# Lemming_v3.net
KiCad netlist of a schematic drawn in EAGLE
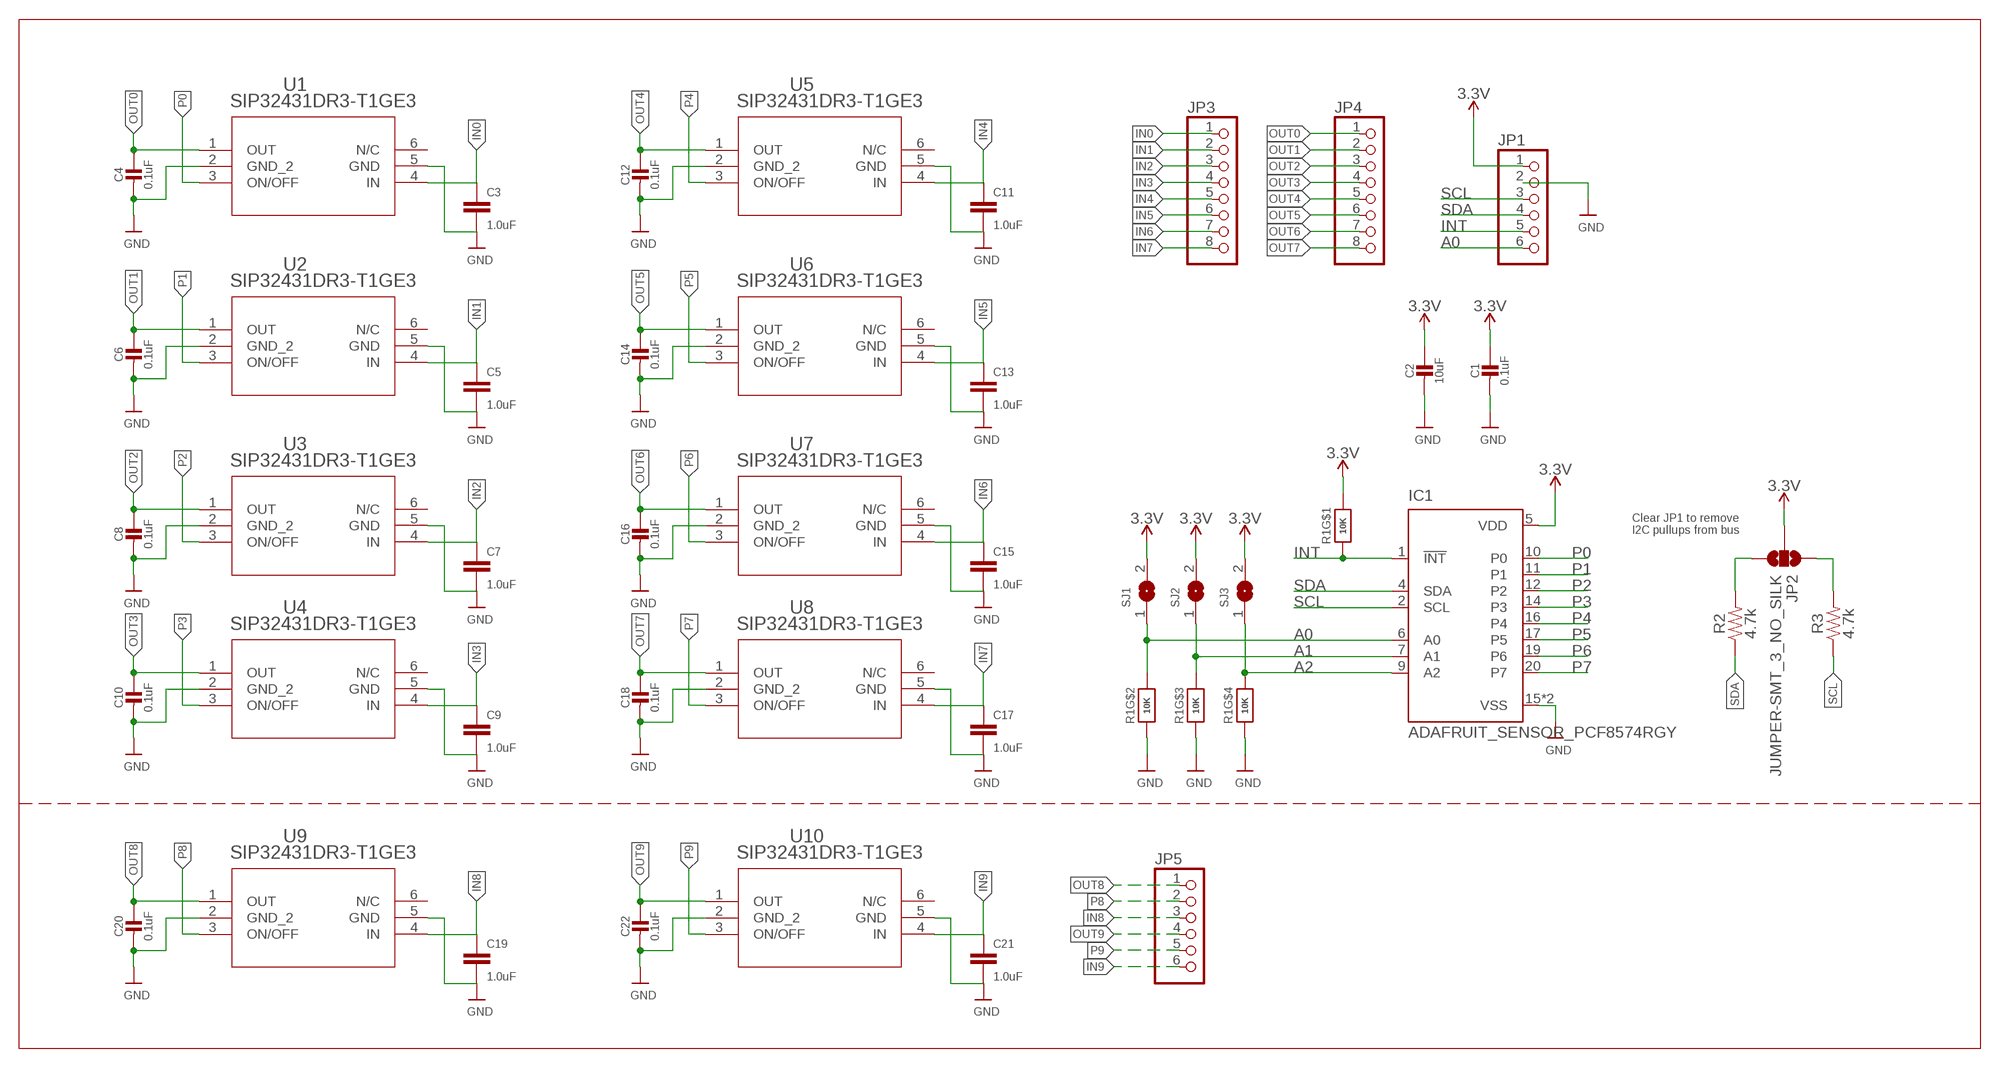
[diagram p0: schematic, sheet 1]

(export (version "E")
  (design (tool "Eeschema 10.0.6"))
  (components
    (comp (ref "C1")
      (value "0.1uF")
      (footprint "eagle-import:0603-NO")
      (libsource (lib "eagle-import") (part "CAP_CERAMIC0603_NO"))
    )
    (comp (ref "C2")
      (value "10uF")
      (footprint "eagle-import:0805-NO")
      (libsource (lib "eagle-import") (part "CAP_CERAMIC0805-NOOUTLINE"))
    )
    (comp (ref "C3")
      (value "1.0uF")
      (footprint "eagle-import:0603")
      (libsource (lib "eagle-import") (part "1.0UF-0603-16V-10%"))
    )
    (comp (ref "C4")
      (value "0.1uF")
      (footprint "eagle-import:0603-NO")
      (libsource (lib "eagle-import") (part "CAP_CERAMIC0603_NO"))
    )
    (comp (ref "C5")
      (value "1.0uF")
      (footprint "eagle-import:0603")
      (libsource (lib "eagle-import") (part "1.0UF-0603-16V-10%"))
    )
    (comp (ref "C6")
      (value "0.1uF")
      (footprint "eagle-import:0603-NO")
      (libsource (lib "eagle-import") (part "CAP_CERAMIC0603_NO"))
    )
    (comp (ref "C7")
      (value "1.0uF")
      (footprint "eagle-import:0603")
      (libsource (lib "eagle-import") (part "1.0UF-0603-16V-10%"))
    )
    (comp (ref "C8")
      (value "0.1uF")
      (footprint "eagle-import:0603-NO")
      (libsource (lib "eagle-import") (part "CAP_CERAMIC0603_NO"))
    )
    (comp (ref "C9")
      (value "1.0uF")
      (footprint "eagle-import:0603")
      (libsource (lib "eagle-import") (part "1.0UF-0603-16V-10%"))
    )
    (comp (ref "C10")
      (value "0.1uF")
      (footprint "eagle-import:0603-NO")
      (libsource (lib "eagle-import") (part "CAP_CERAMIC0603_NO"))
    )
    (comp (ref "C11")
      (value "1.0uF")
      (footprint "eagle-import:0603")
      (libsource (lib "eagle-import") (part "1.0UF-0603-16V-10%"))
    )
    (comp (ref "C12")
      (value "0.1uF")
      (footprint "eagle-import:0603-NO")
      (libsource (lib "eagle-import") (part "CAP_CERAMIC0603_NO"))
    )
    (comp (ref "C13")
      (value "1.0uF")
      (footprint "eagle-import:0603")
      (libsource (lib "eagle-import") (part "1.0UF-0603-16V-10%"))
    )
    (comp (ref "C14")
      (value "0.1uF")
      (footprint "eagle-import:0603-NO")
      (libsource (lib "eagle-import") (part "CAP_CERAMIC0603_NO"))
    )
    (comp (ref "C15")
      (value "1.0uF")
      (footprint "eagle-import:0603")
      (libsource (lib "eagle-import") (part "1.0UF-0603-16V-10%"))
    )
    (comp (ref "C16")
      (value "0.1uF")
      (footprint "eagle-import:0603-NO")
      (libsource (lib "eagle-import") (part "CAP_CERAMIC0603_NO"))
    )
    (comp (ref "C17")
      (value "1.0uF")
      (footprint "eagle-import:0603")
      (libsource (lib "eagle-import") (part "1.0UF-0603-16V-10%"))
    )
    (comp (ref "C18")
      (value "0.1uF")
      (footprint "eagle-import:0603-NO")
      (libsource (lib "eagle-import") (part "CAP_CERAMIC0603_NO"))
    )
    (comp (ref "C19")
      (value "1.0uF")
      (footprint "eagle-import:0603")
      (libsource (lib "eagle-import") (part "1.0UF-0603-16V-10%"))
    )
    (comp (ref "C20")
      (value "0.1uF")
      (footprint "eagle-import:0603-NO")
      (libsource (lib "eagle-import") (part "CAP_CERAMIC0603_NO"))
    )
    (comp (ref "C21")
      (value "1.0uF")
      (footprint "eagle-import:0603")
      (libsource (lib "eagle-import") (part "1.0UF-0603-16V-10%"))
    )
    (comp (ref "C22")
      (value "0.1uF")
      (footprint "eagle-import:0603-NO")
      (libsource (lib "eagle-import") (part "CAP_CERAMIC0603_NO"))
    )
    (comp (ref "IC1")
      (value "ADAFRUIT_SENSOR_PCF8574RGY")
      (footprint "eagle-import:ADAFRUIT_SENSOR_VQFN20_3.5X4.5")
      (libsource (lib "eagle-import") (part "ADAFRUIT_SENSOR_PCF8574RGY"))
    )
    (comp (ref "JP1")
      (value "HEADER-1X670MIL")
      (footprint "eagle-import:1X06_ROUND_70")
      (libsource (lib "eagle-import") (part "HEADER-1X670MIL"))
    )
    (comp (ref "JP2")
      (value "JUMPER-SMT_3_NO_SILK")
      (footprint "eagle-import:SMT-JUMPER_3_NO_SILK")
      (libsource (lib "eagle-import") (part "JUMPER-SMT_3_NO_SILK"))
    )
    (comp (ref "JP3")
      (value "PINHD-1X8BIG")
      (footprint "eagle-import:1X08-BIG")
      (libsource (lib "eagle-import") (part "PINHD-1X8BIG"))
    )
    (comp (ref "JP4")
      (value "PINHD-1X8BIG")
      (footprint "eagle-import:1X08-BIG")
      (libsource (lib "eagle-import") (part "PINHD-1X8BIG"))
    )
    (comp (ref "JP5")
      (value "HEADER-1X670MIL")
      (footprint "eagle-import:1X06_ROUND_70")
      (libsource (lib "eagle-import") (part "HEADER-1X670MIL"))
    )
    (comp (ref "R1")
      (value "10K")
      (footprint "eagle-import:MICROBUILDER_RESPACK_4X0603")
      (libsource (lib "eagle-import") (part "MICROBUILDER_RESISTOR_4PACK"))
    )
    (comp (ref "R2")
      (value "4.7k")
      (footprint "eagle-import:0603")
      (libsource (lib "eagle-import") (part "4.7KOHM-0603-1/10W-1%"))
    )
    (comp (ref "R3")
      (value "4.7k")
      (footprint "eagle-import:0603")
      (libsource (lib "eagle-import") (part "4.7KOHM-0603-1/10W-1%"))
    )
    (comp (ref "SJ1")
      (value "SOLDERJUMPER")
      (footprint "eagle-import:SOLDERJUMPER_ARROW_NOPASTE")
      (libsource (lib "eagle-import") (part "SOLDERJUMPER"))
    )
    (comp (ref "SJ2")
      (value "SOLDERJUMPER")
      (footprint "eagle-import:SOLDERJUMPER_ARROW_NOPASTE")
      (libsource (lib "eagle-import") (part "SOLDERJUMPER"))
    )
    (comp (ref "SJ3")
      (value "SOLDERJUMPER")
      (footprint "eagle-import:SOLDERJUMPER_ARROW_NOPASTE")
      (libsource (lib "eagle-import") (part "SOLDERJUMPER"))
    )
    (comp (ref "U1")
      (value "SIP32431DR3-T1GE3")
      (footprint "eagle-import:SC-70-6_VIS")
      (fields (field (name "COPYRIGHT") "Copyright (C) 2022 Ultra Librarian. All rights reserved."))
      (libsource (lib "eagle-import") (part "SIP32431DR3-T1GE3"))
    )
    (comp (ref "U2")
      (value "SIP32431DR3-T1GE3")
      (footprint "eagle-import:SC-70-6_VIS")
      (fields (field (name "COPYRIGHT") "Copyright (C) 2022 Ultra Librarian. All rights reserved."))
      (libsource (lib "eagle-import") (part "SIP32431DR3-T1GE3"))
    )
    (comp (ref "U3")
      (value "SIP32431DR3-T1GE3")
      (footprint "eagle-import:SC-70-6_VIS")
      (fields (field (name "COPYRIGHT") "Copyright (C) 2022 Ultra Librarian. All rights reserved."))
      (libsource (lib "eagle-import") (part "SIP32431DR3-T1GE3"))
    )
    (comp (ref "U4")
      (value "SIP32431DR3-T1GE3")
      (footprint "eagle-import:SC-70-6_VIS")
      (fields (field (name "COPYRIGHT") "Copyright (C) 2022 Ultra Librarian. All rights reserved."))
      (libsource (lib "eagle-import") (part "SIP32431DR3-T1GE3"))
    )
    (comp (ref "U5")
      (value "SIP32431DR3-T1GE3")
      (footprint "eagle-import:SC-70-6_VIS")
      (fields (field (name "COPYRIGHT") "Copyright (C) 2022 Ultra Librarian. All rights reserved."))
      (libsource (lib "eagle-import") (part "SIP32431DR3-T1GE3"))
    )
    (comp (ref "U6")
      (value "SIP32431DR3-T1GE3")
      (footprint "eagle-import:SC-70-6_VIS")
      (fields (field (name "COPYRIGHT") "Copyright (C) 2022 Ultra Librarian. All rights reserved."))
      (libsource (lib "eagle-import") (part "SIP32431DR3-T1GE3"))
    )
    (comp (ref "U7")
      (value "SIP32431DR3-T1GE3")
      (footprint "eagle-import:SC-70-6_VIS")
      (fields (field (name "COPYRIGHT") "Copyright (C) 2022 Ultra Librarian. All rights reserved."))
      (libsource (lib "eagle-import") (part "SIP32431DR3-T1GE3"))
    )
    (comp (ref "U8")
      (value "SIP32431DR3-T1GE3")
      (footprint "eagle-import:SC-70-6_VIS")
      (fields (field (name "COPYRIGHT") "Copyright (C) 2022 Ultra Librarian. All rights reserved."))
      (libsource (lib "eagle-import") (part "SIP32431DR3-T1GE3"))
    )
    (comp (ref "U9")
      (value "SIP32431DR3-T1GE3")
      (footprint "eagle-import:SC-70-6_VIS")
      (fields (field (name "COPYRIGHT") "Copyright (C) 2022 Ultra Librarian. All rights reserved."))
      (libsource (lib "eagle-import") (part "SIP32431DR3-T1GE3"))
    )
    (comp (ref "U10")
      (value "SIP32431DR3-T1GE3")
      (footprint "eagle-import:SC-70-6_VIS")
      (fields (field (name "COPYRIGHT") "Copyright (C) 2022 Ultra Librarian. All rights reserved."))
      (libsource (lib "eagle-import") (part "SIP32431DR3-T1GE3"))
    )
  )
  (nets
    (net (code "1") (name "/A0") (class "Default")
      (node (ref "IC1") (pin "6") (pinfunction "A0_6") (pintype "input"))
      (node (ref "JP1") (pin "6") (pinfunction "6_6") (pintype "passive"))
      (node (ref "R1") (pin "7") (pinfunction "2_7") (pintype "passive"))
      (node (ref "SJ1") (pin "1") (pinfunction "1_1") (pintype "passive"))
    )
    (net (code "2") (name "/A1") (class "Default")
      (node (ref "IC1") (pin "7") (pinfunction "A1_7") (pintype "input"))
      (node (ref "R1") (pin "6") (pinfunction "2_6") (pintype "passive"))
      (node (ref "SJ2") (pin "1") (pinfunction "1_1") (pintype "passive"))
    )
    (net (code "3") (name "/A2") (class "Default")
      (node (ref "IC1") (pin "9") (pinfunction "A2_9") (pintype "input"))
      (node (ref "R1") (pin "5") (pinfunction "2_5") (pintype "passive"))
      (node (ref "SJ3") (pin "1") (pinfunction "1_1") (pintype "passive"))
    )
    (net (code "4") (name "/INT") (class "Default")
      (node (ref "IC1") (pin "1") (pinfunction "~{INT}_1") (pintype "output"))
      (node (ref "JP1") (pin "5") (pinfunction "5_5") (pintype "passive"))
      (node (ref "R1") (pin "1") (pinfunction "1_1") (pintype "passive"))
    )
    (net (code "5") (name "3.3V") (class "Default")
      (node (ref "C1") (pin "1") (pinfunction "1_1") (pintype "passive"))
      (node (ref "C2") (pin "1") (pinfunction "1_1") (pintype "passive"))
      (node (ref "IC1") (pin "5") (pinfunction "VDD_5") (pintype "power_in"))
      (node (ref "JP1") (pin "1") (pinfunction "1_1") (pintype "passive"))
      (node (ref "JP2") (pin "2") (pinfunction "2_2") (pintype "passive"))
      (node (ref "R1") (pin "8") (pinfunction "2_8") (pintype "passive"))
      (node (ref "SJ1") (pin "2") (pinfunction "2_2") (pintype "passive"))
      (node (ref "SJ2") (pin "2") (pinfunction "2_2") (pintype "passive"))
      (node (ref "SJ3") (pin "2") (pinfunction "2_2") (pintype "passive"))
    )
    (net (code "6") (name "GND") (class "Default")
      (node (ref "C1") (pin "2") (pinfunction "2_2") (pintype "passive"))
      (node (ref "C10") (pin "2") (pinfunction "2_2") (pintype "passive"))
      (node (ref "C11") (pin "2") (pinfunction "2_2") (pintype "passive"))
      (node (ref "C12") (pin "2") (pinfunction "2_2") (pintype "passive"))
      (node (ref "C13") (pin "2") (pinfunction "2_2") (pintype "passive"))
      (node (ref "C14") (pin "2") (pinfunction "2_2") (pintype "passive"))
      (node (ref "C15") (pin "2") (pinfunction "2_2") (pintype "passive"))
      (node (ref "C16") (pin "2") (pinfunction "2_2") (pintype "passive"))
      (node (ref "C17") (pin "2") (pinfunction "2_2") (pintype "passive"))
      (node (ref "C18") (pin "2") (pinfunction "2_2") (pintype "passive"))
      (node (ref "C19") (pin "2") (pinfunction "2_2") (pintype "passive"))
      (node (ref "C2") (pin "2") (pinfunction "2_2") (pintype "passive"))
      (node (ref "C20") (pin "2") (pinfunction "2_2") (pintype "passive"))
      (node (ref "C21") (pin "2") (pinfunction "2_2") (pintype "passive"))
      (node (ref "C22") (pin "2") (pinfunction "2_2") (pintype "passive"))
      (node (ref "C3") (pin "2") (pinfunction "2_2") (pintype "passive"))
      (node (ref "C4") (pin "2") (pinfunction "2_2") (pintype "passive"))
      (node (ref "C5") (pin "2") (pinfunction "2_2") (pintype "passive"))
      (node (ref "C6") (pin "2") (pinfunction "2_2") (pintype "passive"))
      (node (ref "C7") (pin "2") (pinfunction "2_2") (pintype "passive"))
      (node (ref "C8") (pin "2") (pinfunction "2_2") (pintype "passive"))
      (node (ref "C9") (pin "2") (pinfunction "2_2") (pintype "passive"))
      (node (ref "IC1") (pin "15") (pinfunction "VSS_15") (pintype "power_in"))
      (node (ref "IC1") (pin "21") (pinfunction "VSS_21") (pintype "power_in"))
      (node (ref "JP1") (pin "2") (pinfunction "2_2") (pintype "passive"))
      (node (ref "R1") (pin "2") (pinfunction "1_2") (pintype "passive"))
      (node (ref "R1") (pin "3") (pinfunction "1_3") (pintype "passive"))
      (node (ref "R1") (pin "4") (pinfunction "1_4") (pintype "passive"))
      (node (ref "U1") (pin "2") (pinfunction "GND_2_2") (pintype "passive"))
      (node (ref "U1") (pin "5") (pinfunction "GND_5") (pintype "passive"))
      (node (ref "U10") (pin "2") (pinfunction "GND_2_2") (pintype "passive"))
      (node (ref "U10") (pin "5") (pinfunction "GND_5") (pintype "passive"))
      (node (ref "U2") (pin "2") (pinfunction "GND_2_2") (pintype "passive"))
      (node (ref "U2") (pin "5") (pinfunction "GND_5") (pintype "passive"))
      (node (ref "U3") (pin "2") (pinfunction "GND_2_2") (pintype "passive"))
      (node (ref "U3") (pin "5") (pinfunction "GND_5") (pintype "passive"))
      (node (ref "U4") (pin "2") (pinfunction "GND_2_2") (pintype "passive"))
      (node (ref "U4") (pin "5") (pinfunction "GND_5") (pintype "passive"))
      (node (ref "U5") (pin "2") (pinfunction "GND_2_2") (pintype "passive"))
      (node (ref "U5") (pin "5") (pinfunction "GND_5") (pintype "passive"))
      (node (ref "U6") (pin "2") (pinfunction "GND_2_2") (pintype "passive"))
      (node (ref "U6") (pin "5") (pinfunction "GND_5") (pintype "passive"))
      (node (ref "U7") (pin "2") (pinfunction "GND_2_2") (pintype "passive"))
      (node (ref "U7") (pin "5") (pinfunction "GND_5") (pintype "passive"))
      (node (ref "U8") (pin "2") (pinfunction "GND_2_2") (pintype "passive"))
      (node (ref "U8") (pin "5") (pinfunction "GND_5") (pintype "passive"))
      (node (ref "U9") (pin "2") (pinfunction "GND_2_2") (pintype "passive"))
      (node (ref "U9") (pin "5") (pinfunction "GND_5") (pintype "passive"))
    )
    (net (code "7") (name "IN0") (class "Default")
      (node (ref "C3") (pin "1") (pinfunction "1_1") (pintype "passive"))
      (node (ref "JP3") (pin "1") (pinfunction "1_1") (pintype "passive"))
      (node (ref "U1") (pin "4") (pinfunction "IN_4") (pintype "input"))
    )
    (net (code "8") (name "IN1") (class "Default")
      (node (ref "C5") (pin "1") (pinfunction "1_1") (pintype "passive"))
      (node (ref "JP3") (pin "2") (pinfunction "2_2") (pintype "passive"))
      (node (ref "U2") (pin "4") (pinfunction "IN_4") (pintype "input"))
    )
    (net (code "9") (name "IN2") (class "Default")
      (node (ref "C7") (pin "1") (pinfunction "1_1") (pintype "passive"))
      (node (ref "JP3") (pin "3") (pinfunction "3_3") (pintype "passive"))
      (node (ref "U3") (pin "4") (pinfunction "IN_4") (pintype "input"))
    )
    (net (code "10") (name "IN3") (class "Default")
      (node (ref "C9") (pin "1") (pinfunction "1_1") (pintype "passive"))
      (node (ref "JP3") (pin "4") (pinfunction "4_4") (pintype "passive"))
      (node (ref "U4") (pin "4") (pinfunction "IN_4") (pintype "input"))
    )
    (net (code "11") (name "IN4") (class "Default")
      (node (ref "C11") (pin "1") (pinfunction "1_1") (pintype "passive"))
      (node (ref "JP3") (pin "5") (pinfunction "5_5") (pintype "passive"))
      (node (ref "U5") (pin "4") (pinfunction "IN_4") (pintype "input"))
    )
    (net (code "12") (name "IN5") (class "Default")
      (node (ref "C13") (pin "1") (pinfunction "1_1") (pintype "passive"))
      (node (ref "JP3") (pin "6") (pinfunction "6_6") (pintype "passive"))
      (node (ref "U6") (pin "4") (pinfunction "IN_4") (pintype "input"))
    )
    (net (code "13") (name "IN6") (class "Default")
      (node (ref "C15") (pin "1") (pinfunction "1_1") (pintype "passive"))
      (node (ref "JP3") (pin "7") (pinfunction "7_7") (pintype "passive"))
      (node (ref "U7") (pin "4") (pinfunction "IN_4") (pintype "input"))
    )
    (net (code "14") (name "IN7") (class "Default")
      (node (ref "C17") (pin "1") (pinfunction "1_1") (pintype "passive"))
      (node (ref "JP3") (pin "8") (pinfunction "8_8") (pintype "passive"))
      (node (ref "U8") (pin "4") (pinfunction "IN_4") (pintype "input"))
    )
    (net (code "15") (name "IN8") (class "Default")
      (node (ref "C19") (pin "1") (pinfunction "1_1") (pintype "passive"))
      (node (ref "JP5") (pin "3") (pinfunction "3_3") (pintype "passive"))
      (node (ref "U9") (pin "4") (pinfunction "IN_4") (pintype "input"))
    )
    (net (code "16") (name "IN9") (class "Default")
      (node (ref "C21") (pin "1") (pinfunction "1_1") (pintype "passive"))
      (node (ref "JP5") (pin "6") (pinfunction "6_6") (pintype "passive"))
      (node (ref "U10") (pin "4") (pinfunction "IN_4") (pintype "input"))
    )
    (net (code "17") (name "Net-(JP2-Pad1)") (class "Default")
      (node (ref "JP2") (pin "1") (pinfunction "1_1") (pintype "passive"))
      (node (ref "R3") (pin "2") (pinfunction "2_2") (pintype "passive"))
    )
    (net (code "18") (name "Net-(JP2-Pad3)") (class "Default")
      (node (ref "JP2") (pin "3") (pinfunction "3_3") (pintype "passive"))
      (node (ref "R2") (pin "2") (pinfunction "2_2") (pintype "passive"))
    )
    (net (code "19") (name "OUT0") (class "Default")
      (node (ref "C4") (pin "1") (pinfunction "1_1") (pintype "passive"))
      (node (ref "JP4") (pin "1") (pinfunction "1_1") (pintype "passive"))
      (node (ref "U1") (pin "1") (pinfunction "OUT_1") (pintype "output"))
    )
    (net (code "20") (name "OUT1") (class "Default")
      (node (ref "C6") (pin "1") (pinfunction "1_1") (pintype "passive"))
      (node (ref "JP4") (pin "2") (pinfunction "2_2") (pintype "passive"))
      (node (ref "U2") (pin "1") (pinfunction "OUT_1") (pintype "output"))
    )
    (net (code "21") (name "OUT2") (class "Default")
      (node (ref "C8") (pin "1") (pinfunction "1_1") (pintype "passive"))
      (node (ref "JP4") (pin "3") (pinfunction "3_3") (pintype "passive"))
      (node (ref "U3") (pin "1") (pinfunction "OUT_1") (pintype "output"))
    )
    (net (code "22") (name "OUT3") (class "Default")
      (node (ref "C10") (pin "1") (pinfunction "1_1") (pintype "passive"))
      (node (ref "JP4") (pin "4") (pinfunction "4_4") (pintype "passive"))
      (node (ref "U4") (pin "1") (pinfunction "OUT_1") (pintype "output"))
    )
    (net (code "23") (name "OUT4") (class "Default")
      (node (ref "C12") (pin "1") (pinfunction "1_1") (pintype "passive"))
      (node (ref "JP4") (pin "5") (pinfunction "5_5") (pintype "passive"))
      (node (ref "U5") (pin "1") (pinfunction "OUT_1") (pintype "output"))
    )
    (net (code "24") (name "OUT5") (class "Default")
      (node (ref "C14") (pin "1") (pinfunction "1_1") (pintype "passive"))
      (node (ref "JP4") (pin "6") (pinfunction "6_6") (pintype "passive"))
      (node (ref "U6") (pin "1") (pinfunction "OUT_1") (pintype "output"))
    )
    (net (code "25") (name "OUT6") (class "Default")
      (node (ref "C16") (pin "1") (pinfunction "1_1") (pintype "passive"))
      (node (ref "JP4") (pin "7") (pinfunction "7_7") (pintype "passive"))
      (node (ref "U7") (pin "1") (pinfunction "OUT_1") (pintype "output"))
    )
    (net (code "26") (name "OUT7") (class "Default")
      (node (ref "C18") (pin "1") (pinfunction "1_1") (pintype "passive"))
      (node (ref "JP4") (pin "8") (pinfunction "8_8") (pintype "passive"))
      (node (ref "U8") (pin "1") (pinfunction "OUT_1") (pintype "output"))
    )
    (net (code "27") (name "OUT8") (class "Default")
      (node (ref "C20") (pin "1") (pinfunction "1_1") (pintype "passive"))
      (node (ref "JP5") (pin "1") (pinfunction "1_1") (pintype "passive"))
      (node (ref "U9") (pin "1") (pinfunction "OUT_1") (pintype "output"))
    )
    (net (code "28") (name "OUT9") (class "Default")
      (node (ref "C22") (pin "1") (pinfunction "1_1") (pintype "passive"))
      (node (ref "JP5") (pin "4") (pinfunction "4_4") (pintype "passive"))
      (node (ref "U10") (pin "1") (pinfunction "OUT_1") (pintype "output"))
    )
    (net (code "29") (name "P0") (class "Default")
      (node (ref "IC1") (pin "10") (pinfunction "P0_10") (pintype "bidirectional"))
      (node (ref "U1") (pin "3") (pinfunction "ON/OFF_3") (pintype "passive"))
    )
    (net (code "30") (name "P1") (class "Default")
      (node (ref "IC1") (pin "11") (pinfunction "P1_11") (pintype "bidirectional"))
      (node (ref "U2") (pin "3") (pinfunction "ON/OFF_3") (pintype "passive"))
    )
    (net (code "31") (name "P2") (class "Default")
      (node (ref "IC1") (pin "12") (pinfunction "P2_12") (pintype "bidirectional"))
      (node (ref "U3") (pin "3") (pinfunction "ON/OFF_3") (pintype "passive"))
    )
    (net (code "32") (name "P3") (class "Default")
      (node (ref "IC1") (pin "14") (pinfunction "P3_14") (pintype "bidirectional"))
      (node (ref "U4") (pin "3") (pinfunction "ON/OFF_3") (pintype "passive"))
    )
    (net (code "33") (name "P4") (class "Default")
      (node (ref "IC1") (pin "16") (pinfunction "P4_16") (pintype "bidirectional"))
      (node (ref "U5") (pin "3") (pinfunction "ON/OFF_3") (pintype "passive"))
    )
    (net (code "34") (name "P5") (class "Default")
      (node (ref "IC1") (pin "17") (pinfunction "P5_17") (pintype "bidirectional"))
      (node (ref "U6") (pin "3") (pinfunction "ON/OFF_3") (pintype "passive"))
    )
    (net (code "35") (name "P6") (class "Default")
      (node (ref "IC1") (pin "19") (pinfunction "P6_19") (pintype "bidirectional"))
      (node (ref "U7") (pin "3") (pinfunction "ON/OFF_3") (pintype "passive"))
    )
    (net (code "36") (name "P7") (class "Default")
      (node (ref "IC1") (pin "20") (pinfunction "P7_20") (pintype "bidirectional"))
      (node (ref "U8") (pin "3") (pinfunction "ON/OFF_3") (pintype "passive"))
    )
    (net (code "37") (name "P8") (class "Default")
      (node (ref "JP5") (pin "2") (pinfunction "2_2") (pintype "passive"))
      (node (ref "U9") (pin "3") (pinfunction "ON/OFF_3") (pintype "passive"))
    )
    (net (code "38") (name "P9") (class "Default")
      (node (ref "JP5") (pin "5") (pinfunction "5_5") (pintype "passive"))
      (node (ref "U10") (pin "3") (pinfunction "ON/OFF_3") (pintype "passive"))
    )
    (net (code "39") (name "SCL") (class "Default")
      (node (ref "IC1") (pin "2") (pinfunction "SCL_2") (pintype "input"))
      (node (ref "JP1") (pin "3") (pinfunction "3_3") (pintype "passive"))
      (node (ref "R3") (pin "1") (pinfunction "1_1") (pintype "passive"))
    )
    (net (code "40") (name "SDA") (class "Default")
      (node (ref "IC1") (pin "4") (pinfunction "SDA_4") (pintype "bidirectional"))
      (node (ref "JP1") (pin "4") (pinfunction "4_4") (pintype "passive"))
      (node (ref "R2") (pin "1") (pinfunction "1_1") (pintype "passive"))
    )
    (net (code "41") (name "unconnected-(U1-N{slash}C-Pad6)") (class "Default")
      (node (ref "U1") (pin "6") (pinfunction "N/C_6") (pintype "no_connect"))
    )
    (net (code "42") (name "unconnected-(U2-N{slash}C-Pad6)") (class "Default")
      (node (ref "U2") (pin "6") (pinfunction "N/C_6") (pintype "no_connect"))
    )
    (net (code "43") (name "unconnected-(U3-N{slash}C-Pad6)") (class "Default")
      (node (ref "U3") (pin "6") (pinfunction "N/C_6") (pintype "no_connect"))
    )
    (net (code "44") (name "unconnected-(U4-N{slash}C-Pad6)") (class "Default")
      (node (ref "U4") (pin "6") (pinfunction "N/C_6") (pintype "no_connect"))
    )
    (net (code "45") (name "unconnected-(U5-N{slash}C-Pad6)") (class "Default")
      (node (ref "U5") (pin "6") (pinfunction "N/C_6") (pintype "no_connect"))
    )
    (net (code "46") (name "unconnected-(U6-N{slash}C-Pad6)") (class "Default")
      (node (ref "U6") (pin "6") (pinfunction "N/C_6") (pintype "no_connect"))
    )
    (net (code "47") (name "unconnected-(U7-N{slash}C-Pad6)") (class "Default")
      (node (ref "U7") (pin "6") (pinfunction "N/C_6") (pintype "no_connect"))
    )
    (net (code "48") (name "unconnected-(U8-N{slash}C-Pad6)") (class "Default")
      (node (ref "U8") (pin "6") (pinfunction "N/C_6") (pintype "no_connect"))
    )
    (net (code "49") (name "unconnected-(U9-N{slash}C-Pad6)") (class "Default")
      (node (ref "U9") (pin "6") (pinfunction "N/C_6") (pintype "no_connect"))
    )
    (net (code "50") (name "unconnected-(U10-N{slash}C-Pad6)") (class "Default")
      (node (ref "U10") (pin "6") (pinfunction "N/C_6") (pintype "no_connect"))
    )
  )
)
